# minimatrix.net
KiCad netlist of a schematic drawn in EAGLE
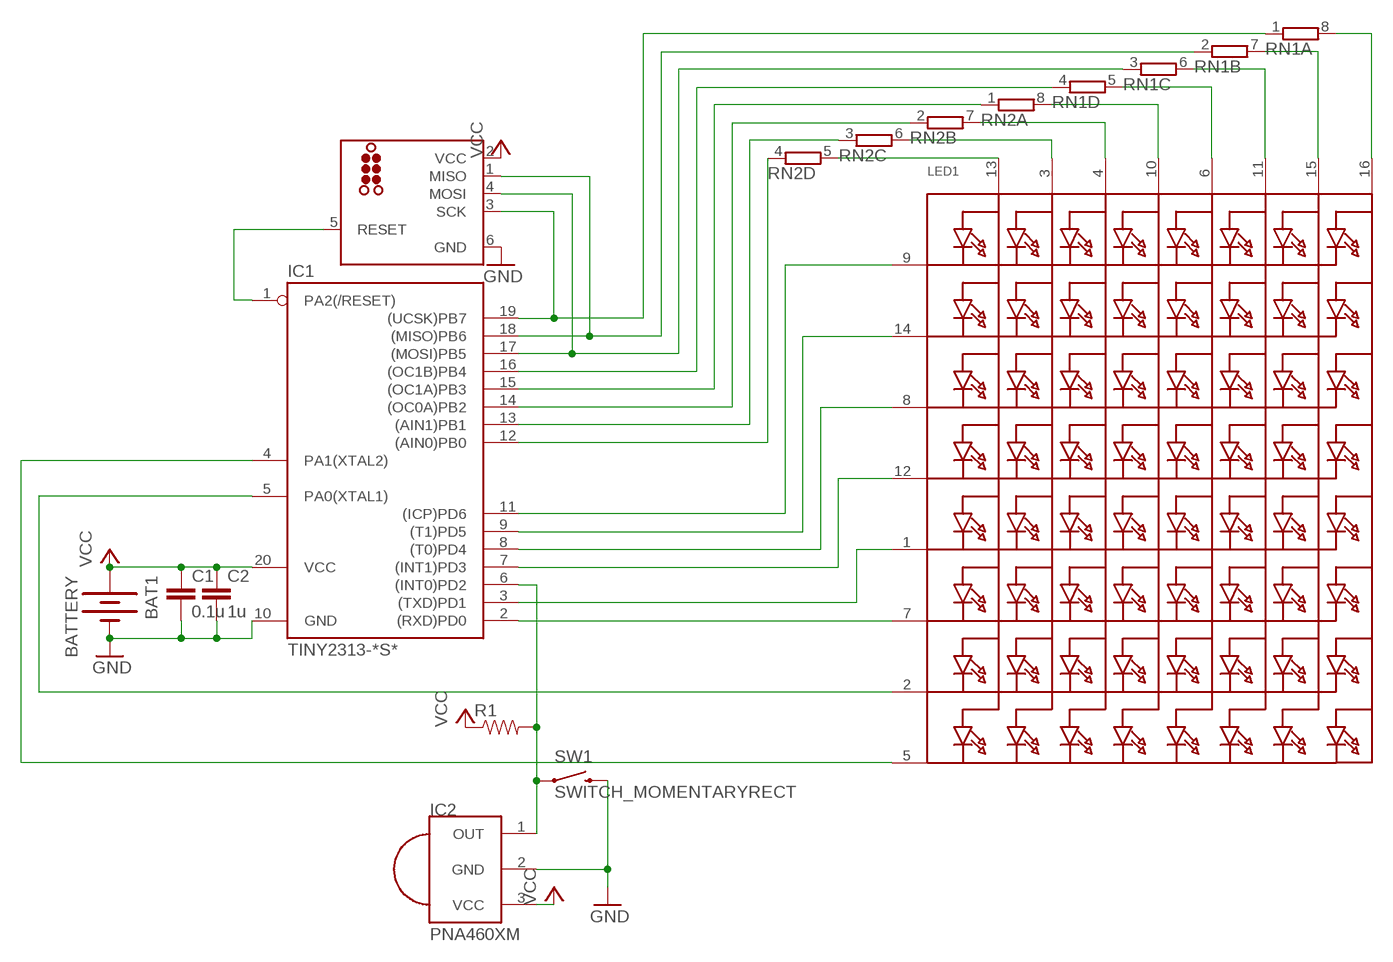
[diagram p0: schematic, sheet 1]

(export (version "E")
  (design (tool "Eeschema 10.0.6"))
  (components
    (comp (ref "BAT1")
      (value "BATTERY")
      (footprint "eagle-import:COINCELL_PTH")
      (libsource (lib "eagle-import") (part "BATTERY"))
    )
    (comp (ref "C1")
      (value "0.1u")
      (footprint "eagle-import:0805")
      (libsource (lib "eagle-import") (part "CAP0805"))
    )
    (comp (ref "C2")
      (value "1u")
      (footprint "eagle-import:0805")
      (libsource (lib "eagle-import") (part "CAP0805"))
    )
    (comp (ref "IC1")
      (value "TINY2313-*S*")
      (footprint "eagle-import:SO20L$")
      (libsource (lib "eagle-import") (part "TINY2313-S"))
    )
    (comp (ref "IC2")
      (value "PNA460XM")
      (footprint "eagle-import:PNA460XM")
      (libsource (lib "eagle-import") (part "PNA460XM"))
    )
    (comp (ref "LED1")
      (value "SEGMENT_8X8_ROWCATHODEM12A881UR")
      (footprint "eagle-import:SEGMENT_BL-M12A881UR")
      (libsource (lib "eagle-import") (part "SEGMENT_8X8_ROWCATHODEM12A881UR"))
    )
    (comp (ref "R1")
      (value "RESISTOR0805-RES")
      (footprint "eagle-import:0805")
      (libsource (lib "eagle-import") (part "RESISTOR0805-RES"))
    )
    (comp (ref "RN1")
      (value "4R-NCAY16")
      (footprint "eagle-import:CAY16")
      (libsource (lib "eagle-import") (part "4R-NCAY16"))
    )
    (comp (ref "RN2")
      (value "4R-NCAY16")
      (footprint "eagle-import:CAY16")
      (libsource (lib "eagle-import") (part "4R-NCAY16"))
    )
    (comp (ref "SW1")
      (value "SWITCH_MOMENTARYRECT")
      (footprint "eagle-import:SWITCH_MOMENTARY_RECT")
      (libsource (lib "eagle-import") (part "SWITCH_MOMENTARYRECT"))
    )
    (comp (ref "U$3")
      (value "TC2030_AVRMCP-NL")
      (footprint "eagle-import:TC2030-MCP-NL")
      (libsource (lib "eagle-import") (part "TC2030_AVRMCP-NL"))
    )
  )
  (nets
    (net (code "1") (name "GND") (class "Default")
      (node (ref "BAT1") (pin "NEG") (pinfunction "-_NEG") (pintype "power_in"))
      (node (ref "C1") (pin "2") (pinfunction "2_2") (pintype "passive"))
      (node (ref "C2") (pin "2") (pinfunction "2_2") (pintype "passive"))
      (node (ref "IC1") (pin "10") (pinfunction "GND_10") (pintype "power_in"))
      (node (ref "IC2") (pin "2") (pinfunction "GND_2") (pintype "power_in"))
      (node (ref "SW1") (pin "P$2") (pinfunction "2_P$2") (pintype "passive"))
      (node (ref "U$3") (pin "6") (pinfunction "GND_6") (pintype "power_in"))
    )
    (net (code "2") (name "Net-(IC1-(AIN0)PB0)") (class "Default")
      (node (ref "IC1") (pin "12") (pinfunction "(AIN0)PB0_12") (pintype "bidirectional"))
      (node (ref "RN2") (pin "4") (pinfunction "1_4") (pintype "passive"))
    )
    (net (code "3") (name "Net-(IC1-(AIN1)PB1)") (class "Default")
      (node (ref "IC1") (pin "13") (pinfunction "(AIN1)PB1_13") (pintype "bidirectional"))
      (node (ref "RN2") (pin "3") (pinfunction "1_3") (pintype "passive"))
    )
    (net (code "4") (name "Net-(IC1-(ICP)PD6)") (class "Default")
      (node (ref "IC1") (pin "11") (pinfunction "(ICP)PD6_11") (pintype "bidirectional"))
      (node (ref "LED1") (pin "9") (pinfunction "K1_9") (pintype "bidirectional"))
    )
    (net (code "5") (name "Net-(IC1-(INT0)PD2)") (class "Default")
      (node (ref "IC1") (pin "6") (pinfunction "(INT0)PD2_6") (pintype "bidirectional"))
      (node (ref "IC2") (pin "1") (pinfunction "OUT_1") (pintype "output"))
      (node (ref "R1") (pin "2") (pinfunction "2_2") (pintype "passive"))
      (node (ref "SW1") (pin "P$1") (pinfunction "1_P$1") (pintype "passive"))
    )
    (net (code "6") (name "Net-(IC1-(INT1)PD3)") (class "Default")
      (node (ref "IC1") (pin "7") (pinfunction "(INT1)PD3_7") (pintype "bidirectional"))
      (node (ref "LED1") (pin "12") (pinfunction "K4_12") (pintype "bidirectional"))
    )
    (net (code "7") (name "Net-(IC1-(MISO)PB6)") (class "Default")
      (node (ref "IC1") (pin "18") (pinfunction "(MISO)PB6_18") (pintype "bidirectional"))
      (node (ref "RN1") (pin "2") (pinfunction "1_2") (pintype "passive"))
      (node (ref "U$3") (pin "1") (pinfunction "MISO_1") (pintype "output"))
    )
    (net (code "8") (name "Net-(IC1-(MOSI)PB5)") (class "Default")
      (node (ref "IC1") (pin "17") (pinfunction "(MOSI)PB5_17") (pintype "bidirectional"))
      (node (ref "RN1") (pin "3") (pinfunction "1_3") (pintype "passive"))
      (node (ref "U$3") (pin "4") (pinfunction "MOSI_4") (pintype "input"))
    )
    (net (code "9") (name "Net-(IC1-(OC0A)PB2)") (class "Default")
      (node (ref "IC1") (pin "14") (pinfunction "(OC0A)PB2_14") (pintype "bidirectional"))
      (node (ref "RN2") (pin "2") (pinfunction "1_2") (pintype "passive"))
    )
    (net (code "10") (name "Net-(IC1-(OC1A)PB3)") (class "Default")
      (node (ref "IC1") (pin "15") (pinfunction "(OC1A)PB3_15") (pintype "bidirectional"))
      (node (ref "RN2") (pin "1") (pinfunction "1_1") (pintype "passive"))
    )
    (net (code "11") (name "Net-(IC1-(OC1B)PB4)") (class "Default")
      (node (ref "IC1") (pin "16") (pinfunction "(OC1B)PB4_16") (pintype "bidirectional"))
      (node (ref "RN1") (pin "4") (pinfunction "1_4") (pintype "passive"))
    )
    (net (code "12") (name "Net-(IC1-(RXD)PD0)") (class "Default")
      (node (ref "IC1") (pin "2") (pinfunction "(RXD)PD0_2") (pintype "bidirectional"))
      (node (ref "LED1") (pin "7") (pinfunction "K6_7") (pintype "bidirectional"))
    )
    (net (code "13") (name "Net-(IC1-(T0)PD4)") (class "Default")
      (node (ref "IC1") (pin "8") (pinfunction "(T0)PD4_8") (pintype "bidirectional"))
      (node (ref "LED1") (pin "8") (pinfunction "K3_8") (pintype "bidirectional"))
    )
    (net (code "14") (name "Net-(IC1-(T1)PD5)") (class "Default")
      (node (ref "IC1") (pin "9") (pinfunction "(T1)PD5_9") (pintype "bidirectional"))
      (node (ref "LED1") (pin "14") (pinfunction "K2_14") (pintype "bidirectional"))
    )
    (net (code "15") (name "Net-(IC1-(TXD)PD1)") (class "Default")
      (node (ref "IC1") (pin "3") (pinfunction "(TXD)PD1_3") (pintype "bidirectional"))
      (node (ref "LED1") (pin "1") (pinfunction "K5_1") (pintype "bidirectional"))
    )
    (net (code "16") (name "Net-(IC1-(UCSK)PB7)") (class "Default")
      (node (ref "IC1") (pin "19") (pinfunction "(UCSK)PB7_19") (pintype "bidirectional"))
      (node (ref "RN1") (pin "1") (pinfunction "1_1") (pintype "passive"))
      (node (ref "U$3") (pin "3") (pinfunction "SCK_3") (pintype "output"))
    )
    (net (code "17") (name "Net-(IC1-PA0(XTAL1))") (class "Default")
      (node (ref "IC1") (pin "5") (pinfunction "PA0(XTAL1)_5") (pintype "bidirectional"))
      (node (ref "LED1") (pin "2") (pinfunction "K7_2") (pintype "bidirectional"))
    )
    (net (code "18") (name "Net-(IC1-PA1(XTAL2))") (class "Default")
      (node (ref "IC1") (pin "4") (pinfunction "PA1(XTAL2)_4") (pintype "bidirectional"))
      (node (ref "LED1") (pin "5") (pinfunction "K8_5") (pintype "bidirectional"))
    )
    (net (code "19") (name "Net-(IC1-PA2({slash}RESET))") (class "Default")
      (node (ref "IC1") (pin "1") (pinfunction "PA2(/RESET)_1") (pintype "input"))
      (node (ref "U$3") (pin "5") (pinfunction "RESET_5") (pintype "output"))
    )
    (net (code "20") (name "Net-(LED1-A1)") (class "Default")
      (node (ref "LED1") (pin "13") (pinfunction "A1_13") (pintype "bidirectional"))
      (node (ref "RN2") (pin "5") (pinfunction "2_5") (pintype "passive"))
    )
    (net (code "21") (name "Net-(LED1-A2)") (class "Default")
      (node (ref "LED1") (pin "3") (pinfunction "A2_3") (pintype "bidirectional"))
      (node (ref "RN2") (pin "6") (pinfunction "2_6") (pintype "passive"))
    )
    (net (code "22") (name "Net-(LED1-A3)") (class "Default")
      (node (ref "LED1") (pin "4") (pinfunction "A3_4") (pintype "bidirectional"))
      (node (ref "RN2") (pin "7") (pinfunction "2_7") (pintype "passive"))
    )
    (net (code "23") (name "Net-(LED1-A4)") (class "Default")
      (node (ref "LED1") (pin "10") (pinfunction "A4_10") (pintype "bidirectional"))
      (node (ref "RN2") (pin "8") (pinfunction "2_8") (pintype "passive"))
    )
    (net (code "24") (name "Net-(LED1-A5)") (class "Default")
      (node (ref "LED1") (pin "6") (pinfunction "A5_6") (pintype "bidirectional"))
      (node (ref "RN1") (pin "5") (pinfunction "2_5") (pintype "passive"))
    )
    (net (code "25") (name "Net-(LED1-A6)") (class "Default")
      (node (ref "LED1") (pin "11") (pinfunction "A6_11") (pintype "bidirectional"))
      (node (ref "RN1") (pin "6") (pinfunction "2_6") (pintype "passive"))
    )
    (net (code "26") (name "Net-(LED1-A7)") (class "Default")
      (node (ref "LED1") (pin "15") (pinfunction "A7_15") (pintype "bidirectional"))
      (node (ref "RN1") (pin "7") (pinfunction "2_7") (pintype "passive"))
    )
    (net (code "27") (name "Net-(LED1-A8)") (class "Default")
      (node (ref "LED1") (pin "16") (pinfunction "A8_16") (pintype "bidirectional"))
      (node (ref "RN1") (pin "8") (pinfunction "2_8") (pintype "passive"))
    )
    (net (code "28") (name "VCC") (class "Default")
      (node (ref "BAT1") (pin "POS1") (pinfunction "+_POS1") (pintype "power_in"))
      (node (ref "BAT1") (pin "POS2") (pinfunction "+_POS2") (pintype "power_in"))
      (node (ref "C1") (pin "1") (pinfunction "1_1") (pintype "passive"))
      (node (ref "C2") (pin "1") (pinfunction "1_1") (pintype "passive"))
      (node (ref "IC1") (pin "20") (pinfunction "VCC_20") (pintype "power_in"))
      (node (ref "IC2") (pin "3") (pinfunction "VCC_3") (pintype "power_in"))
      (node (ref "R1") (pin "1") (pinfunction "1_1") (pintype "passive"))
      (node (ref "U$3") (pin "2") (pinfunction "VCC_2") (pintype "power_in"))
    )
  )
)
